# 06-BatteryManagement.net
KiCad netlist of a schematic drawn in Altium Designer
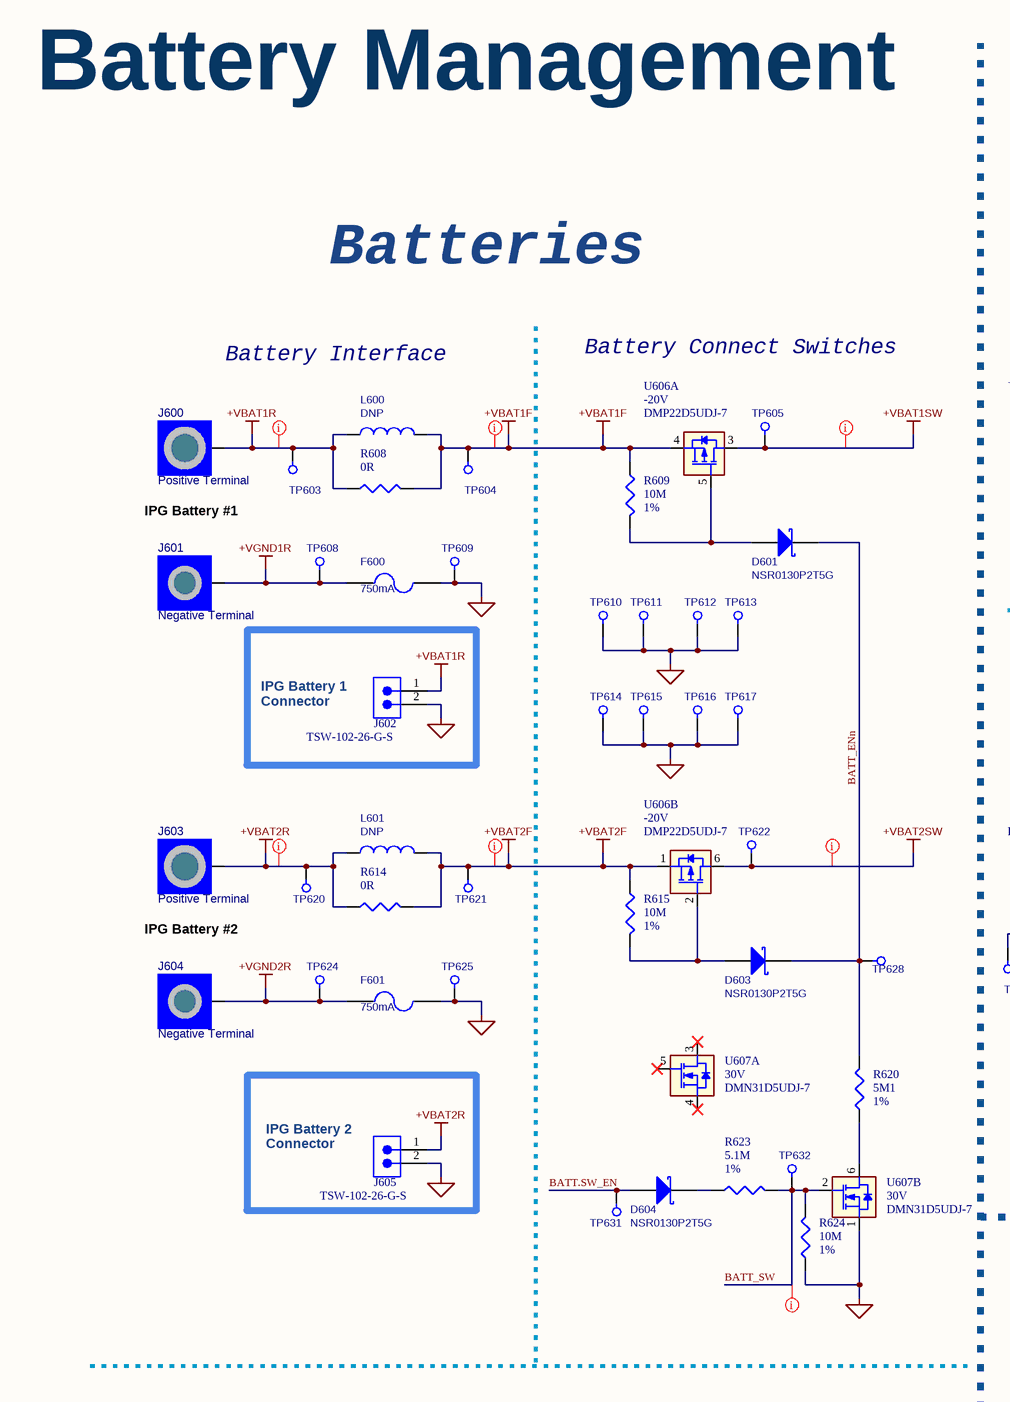
[diagram p0: 06-BatteryManagement.SchDoc, left]
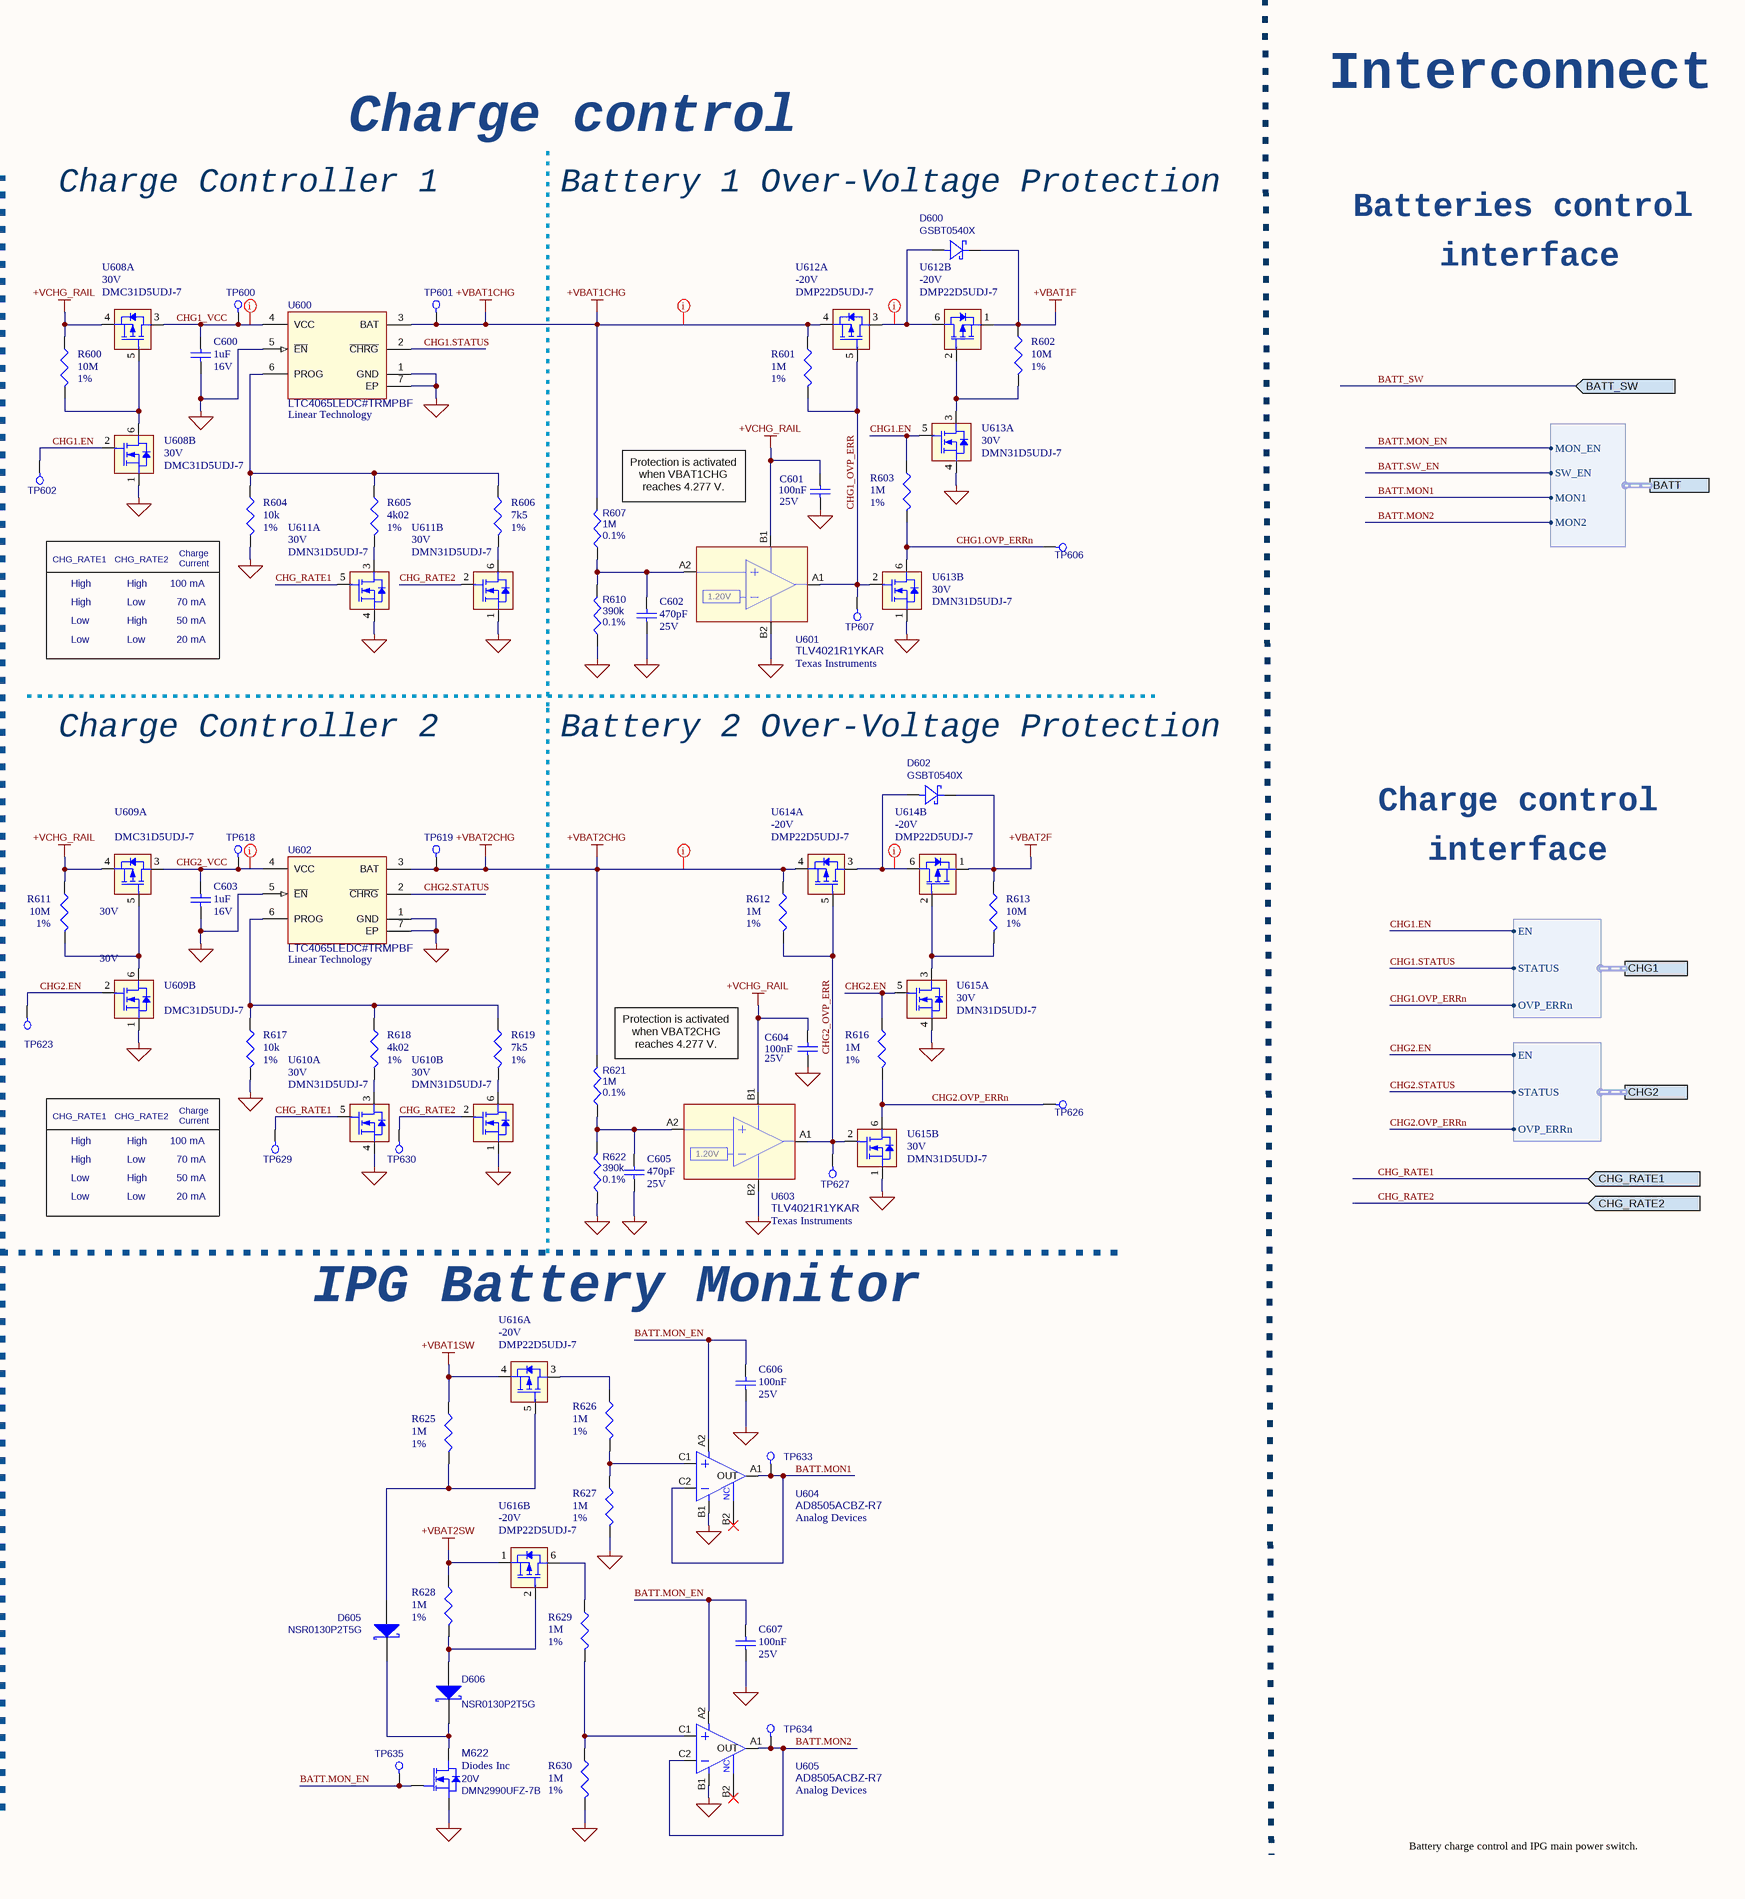
[diagram p1: 06-BatteryManagement.SchDoc, right]

(export (version "E")
  (design (tool "Eeschema 10.0.6"))
  (components
    (comp (ref "C600")
      (value "1uF")
      (footprint "C0201_C")
      (fields
        (field (name "MANUFACTURER") "Murata")
        (field (name "MANUFACTURER PART NUMBER") "GRM033R61C105ME15D")
        (field (name "RATED DC VOLTAGE (URDC)") "16V")
      )
      (libsource (lib "MP-LIBRARY") (part "GRM033R61C105ME15D"))
    )
    (comp (ref "C601")
      (value "100nF")
      (footprint "C0201_C")
      (fields
        (field (name "MANUFACTURER") "Murata")
        (field (name "MANUFACTURER PART NUMBER") "GRM033R61E104KE14J")
        (field (name "RATED DC VOLTAGE (URDC)") "25V")
      )
      (libsource (lib "MP-LIBRARY") (part "GRM033R61E104KE14J"))
    )
    (comp (ref "C602")
      (value "470pF")
      (footprint "C0201_C")
      (fields
        (field (name "MANUFACTURER") "Murata")
        (field (name "MANUFACTURER PART NUMBER") "GCM033R71E471KA03D")
        (field (name "RATED DC VOLTAGE (URDC)") "25V")
      )
      (libsource (lib "MP-LIBRARY") (part "GCM033R71E471KA03D"))
    )
    (comp (ref "C603")
      (value "1uF")
      (footprint "C0201_C")
      (fields
        (field (name "MANUFACTURER") "Murata")
        (field (name "MANUFACTURER PART NUMBER") "GRM033R61C105ME15D")
        (field (name "RATED DC VOLTAGE (URDC)") "16V")
      )
      (libsource (lib "MP-LIBRARY") (part "GRM033R61C105ME15D"))
    )
    (comp (ref "C604")
      (value "100nF")
      (footprint "C0201_C")
      (fields
        (field (name "MANUFACTURER") "Murata")
        (field (name "MANUFACTURER PART NUMBER") "GRM033R61E104KE14J")
        (field (name "RATED DC VOLTAGE (URDC)") "25V")
      )
      (libsource (lib "MP-LIBRARY") (part "GRM033R61E104KE14J"))
    )
    (comp (ref "C605")
      (value "470pF")
      (footprint "C0201_C")
      (fields
        (field (name "MANUFACTURER") "Murata")
        (field (name "MANUFACTURER PART NUMBER") "GCM033R71E471KA03D")
        (field (name "RATED DC VOLTAGE (URDC)") "25V")
      )
      (libsource (lib "MP-LIBRARY") (part "GCM033R71E471KA03D"))
    )
    (comp (ref "C606")
      (value "100nF")
      (footprint "C0201_C")
      (fields
        (field (name "MANUFACTURER") "Murata")
        (field (name "MANUFACTURER PART NUMBER") "GRM033R61E104KE14J")
        (field (name "RATED DC VOLTAGE (URDC)") "25V")
      )
      (libsource (lib "MP-LIBRARY") (part "GRM033R61E104KE14J"))
    )
    (comp (ref "C607")
      (value "100nF")
      (footprint "C0201_C")
      (fields
        (field (name "MANUFACTURER") "Murata")
        (field (name "MANUFACTURER PART NUMBER") "GRM033R61E104KE14J")
        (field (name "RATED DC VOLTAGE (URDC)") "25V")
      )
      (libsource (lib "MP-LIBRARY") (part "GRM033R61E104KE14J"))
    )
    (comp (ref "D600")
      (value "GSBT0540X")
      (footprint "STM_SOD-523_R")
      (description "DIODE SCHOTTKY 40V 500MA SOD523")
      (fields (field (name "MANUFACTURER") "Good-Ark Semiconductor"))
      (libsource (lib "MP-LIBRARY") (part "GSBT0540X"))
    )
    (comp (ref "D601")
      (value "NSR0130P2T5G")
      (footprint "ONSC_SOD-923_CASE514AB")
      (description "Schottky, 30V, 100mA, 385mV, 200mW, SOD-923")
      (fields (field (name "MANUFACTURER") "ON Semiconductor"))
      (libsource (lib "MP-LIBRARY") (part "NSR0130P2T5G"))
    )
    (comp (ref "D602")
      (value "GSBT0540X")
      (footprint "STM_SOD-523_R")
      (description "DIODE SCHOTTKY 40V 500MA SOD523")
      (fields (field (name "MANUFACTURER") "Good-Ark Semiconductor"))
      (libsource (lib "MP-LIBRARY") (part "GSBT0540X"))
    )
    (comp (ref "D603")
      (value "NSR0130P2T5G")
      (footprint "ONSC_SOD-923_CASE514AB")
      (description "Schottky, 30V, 100mA, 385mV, 200mW, SOD-923")
      (fields (field (name "MANUFACTURER") "ON Semiconductor"))
      (libsource (lib "MP-LIBRARY") (part "NSR0130P2T5G"))
    )
    (comp (ref "D604")
      (value "NSR0130P2T5G")
      (footprint "ONSC_SOD-923_CASE514AB")
      (description "Schottky, 30V, 100mA, 385mV, 200mW, SOD-923")
      (fields (field (name "MANUFACTURER") "ON Semiconductor"))
      (libsource (lib "MP-LIBRARY") (part "NSR0130P2T5G"))
    )
    (comp (ref "D605")
      (value "NSR0130P2T5G")
      (footprint "ONSC_SOD-923_CASE514AB")
      (description "Schottky, 30V, 100mA, 385mV, 200mW, SOD-923")
      (fields (field (name "MANUFACTURER") "ON Semiconductor"))
      (libsource (lib "MP-LIBRARY") (part "NSR0130P2T5G"))
    )
    (comp (ref "D606")
      (value "NSR0130P2T5G")
      (footprint "ONSC_SOD-923_CASE514AB")
      (description "Schottky, 30V, 100mA, 385mV, 200mW, SOD-923")
      (fields (field (name "MANUFACTURER") "ON Semiconductor"))
      (libsource (lib "MP-LIBRARY") (part "NSR0130P2T5G"))
    )
    (comp (ref "F600")
      (value "750mA")
      (footprint "LITTELFUSE_440series_1206_REDUCED")
      (description "Fuse, 750mA, 63V, 1206")
      (fields
        (field (name "MANUFACTURER") "Littelfuse")
        (field (name "MANUFACTURER PART NUMBER") "0440.750WR")
      )
      (libsource (lib "MP-LIBRARY") (part "0440.750WR"))
    )
    (comp (ref "F601")
      (value "750mA")
      (footprint "LITTELFUSE_440series_1206_REDUCED")
      (description "Fuse, 750mA, 63V, 1206")
      (fields
        (field (name "MANUFACTURER") "Littelfuse")
        (field (name "MANUFACTURER PART NUMBER") "0440.750WR")
      )
      (libsource (lib "MP-LIBRARY") (part "0440.750WR"))
    )
    (comp (ref "J600")
      (value "Positive Terminal")
      (footprint "Positive_Battery_PTH")
      (description "Positive terminal battery PTH connector for the QL0200I-A battery")
      (fields (field (name "MANUFACTURER") "Quallion") (field (name "MANUFACTURER PART NUMBER") "QL0200I-A"))
      (libsource (lib "MP-LIBRARY") (part "Positive_Battery_PTH"))
    )
    (comp (ref "J601")
      (value "Negative Terminal")
      (footprint "Negative_Battery_PTH")
      (description "Negative terminal battery PTH connector for the QL0200I-A battery")
      (fields (field (name "MANUFACTURER") "Quallion") (field (name "MANUFACTURER PART NUMBER") "QL0200I-A"))
      (libsource (lib "MP-LIBRARY") (part "Negative_Battery_PTH"))
    )
    (comp (ref "J602")
      (value "TSW-102-26-G-S")
      (footprint "SMTC-TSW-102-26-XX-S")
      (description "Conn Unshrouded Header HDR 2 POS 2.54mm Solder ST Thru-Hole")
      (fields (field (name "MANUFACTURER") "Samtec"))
      (libsource (lib "MP-LIBRARY") (part "TSW-102-26-G-S"))
    )
    (comp (ref "J603")
      (value "Positive Terminal")
      (footprint "Positive_Battery_PTH")
      (description "Positive terminal battery PTH connector for the QL0200I-A battery")
      (fields (field (name "MANUFACTURER") "Quallion") (field (name "MANUFACTURER PART NUMBER") "QL0200I-A"))
      (libsource (lib "MP-LIBRARY") (part "Positive_Battery_PTH"))
    )
    (comp (ref "J604")
      (value "Negative Terminal")
      (footprint "Negative_Battery_PTH")
      (description "Negative terminal battery PTH connector for the QL0200I-A battery")
      (fields (field (name "MANUFACTURER") "Quallion") (field (name "MANUFACTURER PART NUMBER") "QL0200I-A"))
      (libsource (lib "MP-LIBRARY") (part "Negative_Battery_PTH"))
    )
    (comp (ref "J605")
      (value "TSW-102-26-G-S")
      (footprint "SMTC-TSW-102-26-XX-S")
      (description "Conn Unshrouded Header HDR 2 POS 2.54mm Solder ST Thru-Hole")
      (fields (field (name "MANUFACTURER") "Samtec"))
      (libsource (lib "MP-LIBRARY") (part "TSW-102-26-G-S"))
    )
    (comp (ref "L600")
      (value "DNP")
      (footprint "L0402_C")
      (description "DNP: Inductor, DNP, 0402")
      (libsource (lib "MP-LIBRARY") (part "IND_DNP_0402"))
    )
    (comp (ref "L601")
      (value "DNP")
      (footprint "L0402_C")
      (description "DNP: Inductor, DNP, 0402")
      (libsource (lib "MP-LIBRARY") (part "IND_DNP_0402"))
    )
    (comp (ref "M622")
      (value "DMN2990UFZ-7B")
      (footprint "DIODESINC_X2-DFN0606-3")
      (description "MOSFET, N-Chan, 20V, 170mA, DFN0606")
      (fields (field (name "MANUFACTURER") "Diodes Inc") (field (name "RATING") "20V"))
      (libsource (lib "MP-LIBRARY") (part "DMN2990UFZ-7B"))
    )
    (comp (ref "R600")
      (value "10M")
      (footprint "R0201_C")
      (fields
        (field (name "MANUFACTURER") "Vishay Draloric")
        (field (name "MANUFACTURER PART NUMBER") "CRCW020110M0FNED")
        (field (name "TOLERANCE") "1%")
        (field (name "POWER") "50mW")
      )
      (libsource (lib "MP-LIBRARY") (part "CRCW020110M0FNED"))
    )
    (comp (ref "R601")
      (value "1M")
      (footprint "R0201_C")
      (fields
        (field (name "MANUFACTURER") "Vishay")
        (field (name "MANUFACTURER PART NUMBER") "CRCW02011M00FNED")
        (field (name "TOLERANCE") "1%")
        (field (name "POWER") "50mW")
      )
      (libsource (lib "MP-LIBRARY") (part "CRCW02011M00FNED"))
    )
    (comp (ref "R602")
      (value "10M")
      (footprint "R0201_C")
      (fields
        (field (name "MANUFACTURER") "Vishay Draloric")
        (field (name "MANUFACTURER PART NUMBER") "CRCW020110M0FNED")
        (field (name "TOLERANCE") "1%")
        (field (name "POWER") "50mW")
      )
      (libsource (lib "MP-LIBRARY") (part "CRCW020110M0FNED"))
    )
    (comp (ref "R603")
      (value "1M")
      (footprint "R0201_C")
      (fields
        (field (name "MANUFACTURER") "Vishay")
        (field (name "MANUFACTURER PART NUMBER") "CRCW02011M00FNED")
        (field (name "TOLERANCE") "1%")
        (field (name "POWER") "50mW")
      )
      (libsource (lib "MP-LIBRARY") (part "CRCW02011M00FNED"))
    )
    (comp (ref "R604")
      (value "10k")
      (footprint "R0201_C")
      (fields
        (field (name "MANUFACTURER") "Vishay")
        (field (name "MANUFACTURER PART NUMBER") "CRCW020110K0FNED")
        (field (name "TOLERANCE") "1%")
        (field (name "POWER") "50mW")
      )
      (libsource (lib "MP-LIBRARY") (part "CRCW020110K0FNED"))
    )
    (comp (ref "R605")
      (value "4k02")
      (footprint "R0201_C")
      (fields
        (field (name "MANUFACTURER") "Vishay")
        (field (name "MANUFACTURER PART NUMBER") "CRCW02014K02FNED")
        (field (name "TOLERANCE") "1%")
        (field (name "POWER") "50mW")
      )
      (libsource (lib "MP-LIBRARY") (part "CRCW02014K02FNED"))
    )
    (comp (ref "R606")
      (value "7k5")
      (footprint "R0201_C")
      (fields
        (field (name "MANUFACTURER") "Vishay")
        (field (name "MANUFACTURER PART NUMBER") "CRCW02017K50FNED")
        (field (name "TOLERANCE") "1%")
        (field (name "POWER") "50mW")
      )
      (libsource (lib "MP-LIBRARY") (part "CRCW02017K50FNED"))
    )
    (comp (ref "R607")
      (value "1M")
      (footprint "R0201_C")
      (description "Resistor, 1M, 0.1%, 0201")
      (fields
        (field (name "MANUFACTURER") "Yageo")
        (field (name "MANUFACTURER PART NUMBER") "RE0201BRE071ML")
        (field (name "PRECISION") "0.1%")
      )
      (libsource (lib "MP-LIBRARY") (part "RE0201BRE071ML"))
    )
    (comp (ref "R608")
      (value "0R")
      (footprint "R0201_C")
      (description "Fixed Resistor, Metal Glaze/thick Film, 0.05W, 0ohm, Surface Mount, 0201")
      (fields
        (field (name "MANUFACTURER") "Vishay")
        (field (name "MANUFACTURER PART NUMBER") "CRCW02010000Z0ED")
      )
      (libsource (lib "MP-LIBRARY") (part "CRCW02010000Z0ED"))
    )
    (comp (ref "R609")
      (value "10M")
      (footprint "R0201_C")
      (fields
        (field (name "MANUFACTURER") "Vishay Draloric")
        (field (name "MANUFACTURER PART NUMBER") "CRCW020110M0FNED")
        (field (name "TOLERANCE") "1%")
        (field (name "POWER") "50mW")
      )
      (libsource (lib "MP-LIBRARY") (part "CRCW020110M0FNED"))
    )
    (comp (ref "R610")
      (value "390k")
      (footprint "R0201_C")
      (description "Resistor, 390k, 0.1%, 0201")
      (fields
        (field (name "MANUFACTURER") "Kamaya")
        (field (name "MANUFACTURER PART NUMBER") "RGC1/20C3903BPA")
        (field (name "PRECISION") "0.1%")
      )
      (libsource (lib "MP-LIBRARY") (part "RGC1/20C3903BPA"))
    )
    (comp (ref "R611")
      (value "10M")
      (footprint "R0201_C")
      (fields
        (field (name "MANUFACTURER") "Vishay Draloric")
        (field (name "MANUFACTURER PART NUMBER") "CRCW020110M0FNED")
        (field (name "TOLERANCE") "1%")
        (field (name "POWER") "50mW")
      )
      (libsource (lib "MP-LIBRARY") (part "CRCW020110M0FNED"))
    )
    (comp (ref "R612")
      (value "1M")
      (footprint "R0201_C")
      (fields
        (field (name "MANUFACTURER") "Vishay")
        (field (name "MANUFACTURER PART NUMBER") "CRCW02011M00FNED")
        (field (name "TOLERANCE") "1%")
        (field (name "POWER") "50mW")
      )
      (libsource (lib "MP-LIBRARY") (part "CRCW02011M00FNED"))
    )
    (comp (ref "R613")
      (value "10M")
      (footprint "R0201_C")
      (fields
        (field (name "MANUFACTURER") "Vishay Draloric")
        (field (name "MANUFACTURER PART NUMBER") "CRCW020110M0FNED")
        (field (name "TOLERANCE") "1%")
        (field (name "POWER") "50mW")
      )
      (libsource (lib "MP-LIBRARY") (part "CRCW020110M0FNED"))
    )
    (comp (ref "R614")
      (value "0R")
      (footprint "R0201_C")
      (description "Fixed Resistor, Metal Glaze/thick Film, 0.05W, 0ohm, Surface Mount, 0201")
      (fields
        (field (name "MANUFACTURER") "Vishay")
        (field (name "MANUFACTURER PART NUMBER") "CRCW02010000Z0ED")
      )
      (libsource (lib "MP-LIBRARY") (part "CRCW02010000Z0ED"))
    )
    (comp (ref "R615")
      (value "10M")
      (footprint "R0201_C")
      (fields
        (field (name "MANUFACTURER") "Vishay Draloric")
        (field (name "MANUFACTURER PART NUMBER") "CRCW020110M0FNED")
        (field (name "TOLERANCE") "1%")
        (field (name "POWER") "50mW")
      )
      (libsource (lib "MP-LIBRARY") (part "CRCW020110M0FNED"))
    )
    (comp (ref "R616")
      (value "1M")
      (footprint "R0201_C")
      (fields
        (field (name "MANUFACTURER") "Vishay")
        (field (name "MANUFACTURER PART NUMBER") "CRCW02011M00FNED")
        (field (name "TOLERANCE") "1%")
        (field (name "POWER") "50mW")
      )
      (libsource (lib "MP-LIBRARY") (part "CRCW02011M00FNED"))
    )
    (comp (ref "R617")
      (value "10k")
      (footprint "R0201_C")
      (fields
        (field (name "MANUFACTURER") "Vishay")
        (field (name "MANUFACTURER PART NUMBER") "CRCW020110K0FNED")
        (field (name "TOLERANCE") "1%")
        (field (name "POWER") "50mW")
      )
      (libsource (lib "MP-LIBRARY") (part "CRCW020110K0FNED"))
    )
    (comp (ref "R618")
      (value "4k02")
      (footprint "R0201_C")
      (fields
        (field (name "MANUFACTURER") "Vishay")
        (field (name "MANUFACTURER PART NUMBER") "CRCW02014K02FNED")
        (field (name "TOLERANCE") "1%")
        (field (name "POWER") "50mW")
      )
      (libsource (lib "MP-LIBRARY") (part "CRCW02014K02FNED"))
    )
    (comp (ref "R619")
      (value "7k5")
      (footprint "R0201_C")
      (fields
        (field (name "MANUFACTURER") "Vishay")
        (field (name "MANUFACTURER PART NUMBER") "CRCW02017K50FNED")
        (field (name "TOLERANCE") "1%")
        (field (name "POWER") "50mW")
      )
      (libsource (lib "MP-LIBRARY") (part "CRCW02017K50FNED"))
    )
    (comp (ref "R620")
      (value "5M1")
      (footprint "R0201_C")
      (fields
        (field (name "MANUFACTURER") "Vishay Draloric")
        (field (name "MANUFACTURER PART NUMBER") "CRCW02015M10FNED")
        (field (name "TOLERANCE") "1%")
        (field (name "POWER") "50mW")
      )
      (libsource (lib "MP-LIBRARY") (part "CRCW02015M10FNED"))
    )
    (comp (ref "R621")
      (value "1M")
      (footprint "R0201_C")
      (description "Resistor, 1M, 0.1%, 0201")
      (fields
        (field (name "MANUFACTURER") "Yageo")
        (field (name "MANUFACTURER PART NUMBER") "RE0201BRE071ML")
        (field (name "PRECISION") "0.1%")
      )
      (libsource (lib "MP-LIBRARY") (part "RE0201BRE071ML"))
    )
    (comp (ref "R622")
      (value "390k")
      (footprint "R0201_C")
      (description "Resistor, 390k, 0.1%, 0201")
      (fields
        (field (name "MANUFACTURER") "Kamaya")
        (field (name "MANUFACTURER PART NUMBER") "RGC1/20C3903BPA")
        (field (name "PRECISION") "0.1%")
      )
      (libsource (lib "MP-LIBRARY") (part "RGC1/20C3903BPA"))
    )
    (comp (ref "R623")
      (value "5.1M")
      (footprint "R0201_C")
      (fields
        (field (name "MANUFACTURER") "Vishay Draloric")
        (field (name "MANUFACTURER PART NUMBER") "CRCW02015M10FNED")
        (field (name "TOLERANCE") "1%")
        (field (name "POWER") "50mW")
      )
      (libsource (lib "MP-LIBRARY") (part "CRCW02015M10FNED"))
    )
    (comp (ref "R624")
      (value "10M")
      (footprint "R0201_C")
      (fields
        (field (name "MANUFACTURER") "Vishay Draloric")
        (field (name "MANUFACTURER PART NUMBER") "CRCW020110M0FNED")
        (field (name "TOLERANCE") "1%")
        (field (name "POWER") "50mW")
      )
      (libsource (lib "MP-LIBRARY") (part "CRCW020110M0FNED"))
    )
    (comp (ref "R625")
      (value "1M")
      (footprint "R0201_C")
      (fields
        (field (name "MANUFACTURER") "Vishay")
        (field (name "MANUFACTURER PART NUMBER") "CRCW02011M00FNED")
        (field (name "TOLERANCE") "1%")
        (field (name "POWER") "50mW")
      )
      (libsource (lib "MP-LIBRARY") (part "CRCW02011M00FNED"))
    )
    (comp (ref "R626")
      (value "1M")
      (footprint "R0201_C")
      (fields
        (field (name "MANUFACTURER") "Vishay")
        (field (name "MANUFACTURER PART NUMBER") "CRCW02011M00FNED")
        (field (name "TOLERANCE") "1%")
        (field (name "POWER") "50mW")
      )
      (libsource (lib "MP-LIBRARY") (part "CRCW02011M00FNED"))
    )
    (comp (ref "R627")
      (value "1M")
      (footprint "R0201_C")
      (fields
        (field (name "MANUFACTURER") "Vishay")
        (field (name "MANUFACTURER PART NUMBER") "CRCW02011M00FNED")
        (field (name "TOLERANCE") "1%")
        (field (name "POWER") "50mW")
      )
      (libsource (lib "MP-LIBRARY") (part "CRCW02011M00FNED"))
    )
    (comp (ref "R628")
      (value "1M")
      (footprint "R0201_C")
      (fields
        (field (name "MANUFACTURER") "Vishay")
        (field (name "MANUFACTURER PART NUMBER") "CRCW02011M00FNED")
        (field (name "TOLERANCE") "1%")
        (field (name "POWER") "50mW")
      )
      (libsource (lib "MP-LIBRARY") (part "CRCW02011M00FNED"))
    )
    (comp (ref "R629")
      (value "1M")
      (footprint "R0201_C")
      (fields
        (field (name "MANUFACTURER") "Vishay")
        (field (name "MANUFACTURER PART NUMBER") "CRCW02011M00FNED")
        (field (name "TOLERANCE") "1%")
        (field (name "POWER") "50mW")
      )
      (libsource (lib "MP-LIBRARY") (part "CRCW02011M00FNED"))
    )
    (comp (ref "R630")
      (value "1M")
      (footprint "R0201_C")
      (fields
        (field (name "MANUFACTURER") "Vishay")
        (field (name "MANUFACTURER PART NUMBER") "CRCW02011M00FNED")
        (field (name "TOLERANCE") "1%")
        (field (name "POWER") "50mW")
      )
      (libsource (lib "MP-LIBRARY") (part "CRCW02011M00FNED"))
    )
    (comp (ref "TP600")
      (value "Test Point")
      (footprint "testpad_0.9mm")
      (description "Test pad, 0.90mm circular pad")
      (libsource (lib "MP-LIBRARY") (part "Test Point"))
    )
    (comp (ref "TP601")
      (value "Test Point")
      (footprint "testpad_0.9mm")
      (description "Test pad, 0.90mm circular pad")
      (libsource (lib "MP-LIBRARY") (part "Test Point"))
    )
    (comp (ref "TP602")
      (value "Test Point")
      (footprint "testpad_0.9mm")
      (description "Test pad, 0.90mm circular pad")
      (libsource (lib "MP-LIBRARY") (part "Test Point"))
    )
    (comp (ref "TP603")
      (value "Test Point")
      (footprint "testpad_0.9mm")
      (description "Test pad, 0.90mm circular pad")
      (libsource (lib "MP-LIBRARY") (part "Test Point"))
    )
    (comp (ref "TP604")
      (value "Test Point")
      (footprint "testpad_0.9mm")
      (description "Test pad, 0.90mm circular pad")
      (libsource (lib "MP-LIBRARY") (part "Test Point"))
    )
    (comp (ref "TP605")
      (value "Test Point")
      (footprint "testpad_0.9mm")
      (description "Test pad, 0.90mm circular pad")
      (libsource (lib "MP-LIBRARY") (part "Test Point"))
    )
    (comp (ref "TP606")
      (value "Test Point")
      (footprint "testpad_0.9mm")
      (description "Test pad, 0.90mm circular pad")
      (libsource (lib "MP-LIBRARY") (part "Test Point"))
    )
    (comp (ref "TP607")
      (value "Test Point")
      (footprint "testpad_0.9mm")
      (description "Test pad, 0.90mm circular pad")
      (libsource (lib "MP-LIBRARY") (part "Test Point"))
    )
    (comp (ref "TP608")
      (value "Test Point")
      (footprint "testpad_0.9mm")
      (description "Test pad, 0.90mm circular pad")
      (libsource (lib "MP-LIBRARY") (part "Test Point"))
    )
    (comp (ref "TP609")
      (value "Test Point")
      (footprint "testpad_0.9mm")
      (description "Test pad, 0.90mm circular pad")
      (libsource (lib "MP-LIBRARY") (part "Test Point"))
    )
    (comp (ref "TP610")
      (value "Test Point")
      (footprint "testpad_0.9mm")
      (description "Test pad, 0.90mm circular pad")
      (libsource (lib "MP-LIBRARY") (part "Test Point"))
    )
    (comp (ref "TP611")
      (value "Test Point")
      (footprint "testpad_0.9mm")
      (description "Test pad, 0.90mm circular pad")
      (libsource (lib "MP-LIBRARY") (part "Test Point"))
    )
    (comp (ref "TP612")
      (value "Test Point")
      (footprint "testpad_0.9mm")
      (description "Test pad, 0.90mm circular pad")
      (libsource (lib "MP-LIBRARY") (part "Test Point"))
    )
    (comp (ref "TP613")
      (value "Test Point")
      (footprint "testpad_0.9mm")
      (description "Test pad, 0.90mm circular pad")
      (libsource (lib "MP-LIBRARY") (part "Test Point"))
    )
    (comp (ref "TP614")
      (value "Test Point")
      (footprint "testpad_0.9mm")
      (description "Test pad, 0.90mm circular pad")
      (libsource (lib "MP-LIBRARY") (part "Test Point"))
    )
    (comp (ref "TP615")
      (value "Test Point")
      (footprint "testpad_0.9mm")
      (description "Test pad, 0.90mm circular pad")
      (libsource (lib "MP-LIBRARY") (part "Test Point"))
    )
    (comp (ref "TP616")
      (value "Test Point")
      (footprint "testpad_0.9mm")
      (description "Test pad, 0.90mm circular pad")
      (libsource (lib "MP-LIBRARY") (part "Test Point"))
    )
    (comp (ref "TP617")
      (value "Test Point")
      (footprint "testpad_0.9mm")
      (description "Test pad, 0.90mm circular pad")
      (libsource (lib "MP-LIBRARY") (part "Test Point"))
    )
    (comp (ref "TP618")
      (value "Test Point")
      (footprint "testpad_0.9mm")
      (description "Test pad, 0.90mm circular pad")
      (libsource (lib "MP-LIBRARY") (part "Test Point"))
    )
    (comp (ref "TP619")
      (value "Test Point")
      (footprint "testpad_0.9mm")
      (description "Test pad, 0.90mm circular pad")
      (libsource (lib "MP-LIBRARY") (part "Test Point"))
    )
    (comp (ref "TP620")
      (value "Test Point")
      (footprint "testpad_0.9mm")
      (description "Test pad, 0.90mm circular pad")
      (libsource (lib "MP-LIBRARY") (part "Test Point"))
    )
    (comp (ref "TP621")
      (value "Test Point")
      (footprint "testpad_0.9mm")
      (description "Test pad, 0.90mm circular pad")
      (libsource (lib "MP-LIBRARY") (part "Test Point"))
    )
    (comp (ref "TP622")
      (value "Test Point")
      (footprint "testpad_0.9mm")
      (description "Test pad, 0.90mm circular pad")
      (libsource (lib "MP-LIBRARY") (part "Test Point"))
    )
    (comp (ref "TP623")
      (value "Test Point")
      (footprint "testpad_0.9mm")
      (description "Test pad, 0.90mm circular pad")
      (libsource (lib "MP-LIBRARY") (part "Test Point"))
    )
    (comp (ref "TP624")
      (value "Test Point")
      (footprint "testpad_0.9mm")
      (description "Test pad, 0.90mm circular pad")
      (libsource (lib "MP-LIBRARY") (part "Test Point"))
    )
    (comp (ref "TP625")
      (value "Test Point")
      (footprint "testpad_0.9mm")
      (description "Test pad, 0.90mm circular pad")
      (libsource (lib "MP-LIBRARY") (part "Test Point"))
    )
    (comp (ref "TP626")
      (value "Test Point")
      (footprint "testpad_0.9mm")
      (description "Test pad, 0.90mm circular pad")
      (libsource (lib "MP-LIBRARY") (part "Test Point"))
    )
    (comp (ref "TP627")
      (value "Test Point")
      (footprint "testpad_0.9mm")
      (description "Test pad, 0.90mm circular pad")
      (libsource (lib "MP-LIBRARY") (part "Test Point"))
    )
    (comp (ref "TP628")
      (value "Test Point")
      (footprint "testpad_0.9mm")
      (description "Test pad, 0.90mm circular pad")
      (libsource (lib "MP-LIBRARY") (part "Test Point"))
    )
    (comp (ref "TP629")
      (value "Test Point")
      (footprint "testpad_0.9mm")
      (description "Test pad, 0.90mm circular pad")
      (libsource (lib "MP-LIBRARY") (part "Test Point"))
    )
    (comp (ref "TP630")
      (value "Test Point")
      (footprint "testpad_0.9mm")
      (description "Test pad, 0.90mm circular pad")
      (libsource (lib "MP-LIBRARY") (part "Test Point"))
    )
    (comp (ref "TP631")
      (value "Test Point")
      (footprint "testpad_0.9mm")
      (description "Test pad, 0.90mm circular pad")
      (libsource (lib "MP-LIBRARY") (part "Test Point"))
    )
    (comp (ref "TP632")
      (value "Test Point")
      (footprint "testpad_0.9mm")
      (description "Test pad, 0.90mm circular pad")
      (libsource (lib "MP-LIBRARY") (part "Test Point"))
    )
    (comp (ref "TP633")
      (value "Test Point")
      (footprint "testpad_0.9mm")
      (description "Test pad, 0.90mm circular pad")
      (libsource (lib "MP-LIBRARY") (part "Test Point"))
    )
    (comp (ref "TP634")
      (value "Test Point")
      (footprint "testpad_0.9mm")
      (description "Test pad, 0.90mm circular pad")
      (libsource (lib "MP-LIBRARY") (part "Test Point"))
    )
    (comp (ref "TP635")
      (value "Test Point")
      (footprint "testpad_0.9mm")
      (description "Test pad, 0.90mm circular pad")
      (libsource (lib "MP-LIBRARY") (part "Test Point"))
    )
    (comp (ref "U600")
      (value "LTC4065LEDC#TRMPBF")
      (footprint "LT_DC6")
      (description "Charge Controller, 4.2V, 250mA, DFN-6")
      (fields
        (field (name "MANUFACTURER") "Linear Technology")
        (field (name "MANUFACTURER PART NUMBER") "LTC4065LEDC#TRPBF")
      )
      (libsource (lib "MP-LIBRARY") (part "LTC4065LEDC#TRPBF"))
    )
    (comp (ref "U601")
      (value "TLV4021R1YKAR")
      (footprint "TI_YKA0004")
      (description "Comparator, 1.2V Reference, Open-drain, BGA-4")
      (fields (field (name "MANUFACTURER") "Texas Instruments"))
      (libsource (lib "MP-LIBRARY") (part "TLV4021R1YKAR"))
    )
    (comp (ref "U602")
      (value "LTC4065LEDC#TRMPBF")
      (footprint "LT_DC6")
      (description "Charge Controller, 4.2V, 250mA, DFN-6")
      (fields
        (field (name "MANUFACTURER") "Linear Technology")
        (field (name "MANUFACTURER PART NUMBER") "LTC4065LEDC#TRPBF")
      )
      (libsource (lib "MP-LIBRARY") (part "LTC4065LEDC#TRPBF"))
    )
    (comp (ref "U603")
      (value "TLV4021R1YKAR")
      (footprint "TI_YKA0004")
      (description "Comparator, 1.2V Reference, Open-drain, BGA-4")
      (fields (field (name "MANUFACTURER") "Texas Instruments"))
      (libsource (lib "MP-LIBRARY") (part "TLV4021R1YKAR"))
    )
    (comp (ref "U604")
      (value "AD8505ACBZ-R7")
      (footprint "AD8505ACBZ-R7")
      (description "Op Amp, Rail-to-Rail, 95kHz, WLCSP-6")
      (fields (field (name "MANUFACTURER") "Analog Devices"))
      (libsource (lib "MP-LIBRARY") (part "AD8505ACBZ-R7"))
    )
    (comp (ref "U605")
      (value "AD8505ACBZ-R7")
      (footprint "AD8505ACBZ-R7")
      (description "Op Amp, Rail-to-Rail, 95kHz, WLCSP-6")
      (fields (field (name "MANUFACTURER") "Analog Devices"))
      (libsource (lib "MP-LIBRARY") (part "AD8505ACBZ-R7"))
    )
    (comp (ref "U606")
      (value "DMP22D5UDJ-7")
      (footprint "DIODESINC_SOT-963-6")
      (description "MOSFET 2P-CH 20V 0.36A SOT963")
      (fields (field (name "MANUFACTURER") "Diodes inc.") (field (name "VDS(MAX)") "-20V"))
      (libsource (lib "") (part "DMP22D5UDJ-7_1"))
    )
    (comp (ref "U607")
      (value "DMN31D5UDJ-7")
      (footprint "DIODESINC_SOT-963-6")
      (description "MOSFET 2N-CH 30V 0.22A SOT963")
      (fields (field (name "MANUFACTURER") "Diodes inc.") (field (name "VDS(MAX)") "30V"))
      (libsource (lib "MP-LIBRARY") (part "DMN31D5UDJ-7"))
    )
    (comp (ref "U608")
      (value "DMC31D5UDJ-7")
      (footprint "DIODESINC_SOT-963-6")
      (description "MOSFET N/P-CH 30V 0.22A SOT963")
      (fields (field (name "MANUFACTURER") "Diodes inc.") (field (name "VDS(MAX)") "30V"))
      (libsource (lib "MP-LIBRARY") (part "DMC31D5UDJ-7"))
    )
    (comp (ref "U609")
      (value "DMC31D5UDJ-7")
      (footprint "DIODESINC_SOT-963-6")
      (description "MOSFET N/P-CH 30V 0.22A SOT963")
      (fields (field (name "MANUFACTURER") "Diodes inc.") (field (name "VDS(MAX)") "30V"))
      (libsource (lib "MP-LIBRARY") (part "DMC31D5UDJ-7"))
    )
    (comp (ref "U610")
      (value "DMN31D5UDJ-7")
      (footprint "DIODESINC_SOT-963-6")
      (description "MOSFET 2N-CH 30V 0.22A SOT963")
      (fields (field (name "MANUFACTURER") "Diodes inc.") (field (name "VDS(MAX)") "30V"))
      (libsource (lib "MP-LIBRARY") (part "DMN31D5UDJ-7"))
    )
    (comp (ref "U611")
      (value "DMN31D5UDJ-7")
      (footprint "DIODESINC_SOT-963-6")
      (description "MOSFET 2N-CH 30V 0.22A SOT963")
      (fields (field (name "MANUFACTURER") "Diodes inc.") (field (name "VDS(MAX)") "30V"))
      (libsource (lib "MP-LIBRARY") (part "DMN31D5UDJ-7"))
    )
    (comp (ref "U612")
      (value "DMP22D5UDJ-7")
      (footprint "DIODESINC_SOT-963-6")
      (description "MOSFET 2P-CH 20V 0.36A SOT963")
      (fields (field (name "MANUFACTURER") "Diodes inc.") (field (name "VDS(MAX)") "-20V"))
      (libsource (lib "") (part "DMP22D5UDJ-7_1"))
    )
    (comp (ref "U613")
      (value "DMN31D5UDJ-7")
      (footprint "DIODESINC_SOT-963-6")
      (description "MOSFET 2N-CH 30V 0.22A SOT963")
      (fields (field (name "MANUFACTURER") "Diodes inc.") (field (name "VDS(MAX)") "30V"))
      (libsource (lib "MP-LIBRARY") (part "DMN31D5UDJ-7"))
    )
    (comp (ref "U614")
      (value "DMP22D5UDJ-7")
      (footprint "DIODESINC_SOT-963-6")
      (description "MOSFET 2P-CH 20V 0.36A SOT963")
      (fields (field (name "MANUFACTURER") "Diodes inc.") (field (name "VDS(MAX)") "-20V"))
      (libsource (lib "MP-LIBRARY") (part "DMP22D5UDJ-7"))
    )
    (comp (ref "U615")
      (value "DMN31D5UDJ-7")
      (footprint "DIODESINC_SOT-963-6")
      (description "MOSFET 2N-CH 30V 0.22A SOT963")
      (fields (field (name "MANUFACTURER") "Diodes inc.") (field (name "VDS(MAX)") "30V"))
      (libsource (lib "MP-LIBRARY") (part "DMN31D5UDJ-7"))
    )
    (comp (ref "U616")
      (value "DMP22D5UDJ-7")
      (footprint "DIODESINC_SOT-963-6")
      (description "MOSFET 2P-CH 20V 0.36A SOT963")
      (fields (field (name "MANUFACTURER") "Diodes inc.") (field (name "VDS(MAX)") "-20V"))
      (libsource (lib "") (part "DMP22D5UDJ-7_1"))
    )
  )
  (nets
    (net (code "3") (name "+VBAT1CHG") (class "Default")
      (node (ref "R601") (pin "1") (pinfunction "1_1") (pintype "passive"))
      (node (ref "R607") (pin "2") (pinfunction "2_2") (pintype "passive"))
      (node (ref "TP601") (pin "1") (pinfunction "1_1") (pintype "passive"))
      (node (ref "U600") (pin "3") (pinfunction "BAT_3") (pintype "power_in"))
      (node (ref "U612") (pin "4") (pinfunction "4_4") (pintype "passive"))
    )
    (net (code "4") (name "+VBAT1F") (class "Default")
      (node (ref "D600") (pin "1") (pinfunction "1_1") (pintype "passive"))
      (node (ref "L600") (pin "2") (pinfunction "2_2") (pintype "passive"))
      (node (ref "R602") (pin "1") (pinfunction "1_1") (pintype "passive"))
      (node (ref "R608") (pin "2") (pinfunction "2_2") (pintype "passive"))
      (node (ref "R609") (pin "1") (pinfunction "1_1") (pintype "passive"))
      (node (ref "TP604") (pin "1") (pinfunction "1_1") (pintype "passive"))
      (node (ref "U606") (pin "4") (pinfunction "4_4") (pintype "passive"))
      (node (ref "U612") (pin "1") (pinfunction "1_1") (pintype "passive"))
    )
    (net (code "5") (name "+VBAT1R") (class "Default")
      (node (ref "J600") (pin "1") (pinfunction "1_1") (pintype "passive"))
      (node (ref "J602") (pin "1") (pinfunction "1_1") (pintype "passive"))
      (node (ref "L600") (pin "1") (pinfunction "1_1") (pintype "passive"))
      (node (ref "R608") (pin "1") (pinfunction "1_1") (pintype "passive"))
      (node (ref "TP603") (pin "1") (pinfunction "1_1") (pintype "passive"))
    )
    (net (code "6") (name "+VBAT1SW") (class "Default")
      (node (ref "R625") (pin "1") (pinfunction "1_1") (pintype "passive"))
      (node (ref "TP605") (pin "1") (pinfunction "1_1") (pintype "passive"))
      (node (ref "U606") (pin "3") (pinfunction "3_3") (pintype "passive"))
      (node (ref "U616") (pin "4") (pinfunction "4_4") (pintype "passive"))
    )
    (net (code "7") (name "+VBAT2CHG") (class "Default")
      (node (ref "R612") (pin "1") (pinfunction "1_1") (pintype "passive"))
      (node (ref "R621") (pin "2") (pinfunction "2_2") (pintype "passive"))
      (node (ref "TP619") (pin "1") (pinfunction "1_1") (pintype "passive"))
      (node (ref "U602") (pin "3") (pinfunction "BAT_3") (pintype "power_in"))
      (node (ref "U614") (pin "4") (pinfunction "4_4") (pintype "passive"))
    )
    (net (code "8") (name "+VBAT2F") (class "Default")
      (node (ref "D602") (pin "1") (pinfunction "1_1") (pintype "passive"))
      (node (ref "L601") (pin "2") (pinfunction "2_2") (pintype "passive"))
      (node (ref "R613") (pin "1") (pinfunction "1_1") (pintype "passive"))
      (node (ref "R614") (pin "2") (pinfunction "2_2") (pintype "passive"))
      (node (ref "R615") (pin "1") (pinfunction "1_1") (pintype "passive"))
      (node (ref "TP621") (pin "1") (pinfunction "1_1") (pintype "passive"))
      (node (ref "U606") (pin "1") (pinfunction "1_1") (pintype "passive"))
      (node (ref "U614") (pin "1") (pinfunction "1_1") (pintype "passive"))
    )
    (net (code "9") (name "+VBAT2R") (class "Default")
      (node (ref "J603") (pin "1") (pinfunction "1_1") (pintype "passive"))
      (node (ref "J605") (pin "1") (pinfunction "1_1") (pintype "passive"))
      (node (ref "L601") (pin "1") (pinfunction "1_1") (pintype "passive"))
      (node (ref "R614") (pin "1") (pinfunction "1_1") (pintype "passive"))
      (node (ref "TP620") (pin "1") (pinfunction "1_1") (pintype "passive"))
    )
    (net (code "10") (name "+VBAT2SW") (class "Default")
      (node (ref "R628") (pin "1") (pinfunction "1_1") (pintype "passive"))
      (node (ref "TP622") (pin "1") (pinfunction "1_1") (pintype "passive"))
      (node (ref "U606") (pin "6") (pinfunction "6_6") (pintype "passive"))
      (node (ref "U616") (pin "1") (pinfunction "1_1") (pintype "passive"))
    )
    (net (code "11") (name "+VCHG_RAIL") (class "Default")
      (node (ref "C601") (pin "2") (pinfunction "2_2") (pintype "passive"))
      (node (ref "C604") (pin "2") (pinfunction "2_2") (pintype "passive"))
      (node (ref "R600") (pin "1") (pinfunction "1_1") (pintype "passive"))
      (node (ref "R611") (pin "1") (pinfunction "1_1") (pintype "passive"))
      (node (ref "U601") (pin "B1") (pinfunction "V+_B1") (pintype "power_in"))
      (node (ref "U603") (pin "B1") (pinfunction "V+_B1") (pintype "power_in"))
      (node (ref "U608") (pin "4") (pinfunction "4_4") (pintype "passive"))
      (node (ref "U609") (pin "4") (pinfunction "4_4") (pintype "passive"))
    )
    (net (code "12") (name "+VGND1R") (class "Default")
      (node (ref "F600") (pin "1") (pinfunction "1_1") (pintype "passive"))
      (node (ref "J601") (pin "1") (pinfunction "1_1") (pintype "passive"))
      (node (ref "TP608") (pin "1") (pinfunction "1_1") (pintype "passive"))
    )
    (net (code "13") (name "+VGND2R") (class "Default")
      (node (ref "F601") (pin "1") (pinfunction "1_1") (pintype "passive"))
      (node (ref "J604") (pin "1") (pinfunction "1_1") (pintype "passive"))
      (node (ref "TP624") (pin "1") (pinfunction "1_1") (pintype "passive"))
    )
    (net (code "14") (name "/BATT.MON1") (class "Default")
      (node (ref "TP633") (pin "1") (pinfunction "1_1") (pintype "passive"))
      (node (ref "U604") (pin "A1") (pinfunction "OUT_A1") (pintype "passive"))
      (node (ref "U604") (pin "C2") (pinfunction "IN-_C2") (pintype "passive"))
    )
    (net (code "15") (name "/BATT.MON2") (class "Default")
      (node (ref "TP634") (pin "1") (pinfunction "1_1") (pintype "passive"))
      (node (ref "U605") (pin "A1") (pinfunction "OUT_A1") (pintype "passive"))
      (node (ref "U605") (pin "C2") (pinfunction "IN-_C2") (pintype "passive"))
    )
    (net (code "16") (name "/BATT.MON_EN") (class "Default")
      (node (ref "C606") (pin "2") (pinfunction "2_2") (pintype "passive"))
      (node (ref "C607") (pin "2") (pinfunction "2_2") (pintype "passive"))
      (node (ref "M622") (pin "1") (pinfunction "G_1") (pintype "passive"))
      (node (ref "TP635") (pin "1") (pinfunction "1_1") (pintype "passive"))
      (node (ref "U604") (pin "A2") (pinfunction "V+_A2") (pintype "power_in"))
      (node (ref "U605") (pin "A2") (pinfunction "V+_A2") (pintype "power_in"))
    )
    (net (code "17") (name "/BATT.SW_EN") (class "Default")
      (node (ref "D604") (pin "2") (pinfunction "A_2") (pintype "passive"))
      (node (ref "TP631") (pin "1") (pinfunction "1_1") (pintype "passive"))
    )
    (net (code "18") (name "/BATT_ENn") (class "Default")
      (node (ref "D601") (pin "1") (pinfunction "K_1") (pintype "passive"))
      (node (ref "D603") (pin "1") (pinfunction "K_1") (pintype "passive"))
      (node (ref "R620") (pin "2") (pinfunction "2_2") (pintype "passive"))
      (node (ref "TP628") (pin "1") (pinfunction "1_1") (pintype "passive"))
    )
    (net (code "19") (name "/BATT_SW") (class "Default")
      (node (ref "R623") (pin "2") (pinfunction "2_2") (pintype "passive"))
      (node (ref "R624") (pin "2") (pinfunction "2_2") (pintype "passive"))
      (node (ref "TP632") (pin "1") (pinfunction "1_1") (pintype "passive"))
      (node (ref "U607") (pin "2") (pinfunction "2_2") (pintype "passive"))
    )
    (net (code "20") (name "/CHG1.EN") (class "Default")
      (node (ref "R603") (pin "1") (pinfunction "1_1") (pintype "passive"))
      (node (ref "TP602") (pin "1") (pinfunction "1_1") (pintype "passive"))
      (node (ref "U608") (pin "2") (pinfunction "2_2") (pintype "passive"))
      (node (ref "U613") (pin "5") (pinfunction "5_5") (pintype "passive"))
    )
    (net (code "21") (name "/CHG1.OVP_ERRn") (class "Default")
      (node (ref "R603") (pin "2") (pinfunction "2_2") (pintype "passive"))
      (node (ref "TP606") (pin "1") (pinfunction "1_1") (pintype "passive"))
      (node (ref "U613") (pin "6") (pinfunction "6_6") (pintype "passive"))
    )
    (net (code "22") (name "/CHG1.STATUS") (class "Default")
      (node (ref "U600") (pin "2") (pinfunction "~{CHRG}_2") (pintype "open_collector"))
    )
    (net (code "23") (name "/CHG1_OVP_ERR") (class "Default")
      (node (ref "R601") (pin "2") (pinfunction "2_2") (pintype "passive"))
      (node (ref "TP607") (pin "1") (pinfunction "1_1") (pintype "passive"))
      (node (ref "U601") (pin "A1") (pinfunction "OUT_A1") (pintype "power_in"))
      (node (ref "U612") (pin "5") (pinfunction "5_5") (pintype "passive"))
      (node (ref "U613") (pin "2") (pinfunction "2_2") (pintype "passive"))
    )
    (net (code "24") (name "/CHG1_VCC") (class "Default")
      (node (ref "C600") (pin "1") (pinfunction "1_1") (pintype "passive"))
      (node (ref "TP600") (pin "1") (pinfunction "1_1") (pintype "passive"))
      (node (ref "U600") (pin "4") (pinfunction "VCC_4") (pintype "power_in"))
      (node (ref "U608") (pin "3") (pinfunction "3_3") (pintype "passive"))
    )
    (net (code "25") (name "/CHG2.EN") (class "Default")
      (node (ref "R616") (pin "1") (pinfunction "1_1") (pintype "passive"))
      (node (ref "TP623") (pin "1") (pinfunction "1_1") (pintype "passive"))
      (node (ref "U609") (pin "2") (pinfunction "2_2") (pintype "passive"))
      (node (ref "U615") (pin "5") (pinfunction "5_5") (pintype "passive"))
    )
    (net (code "26") (name "/CHG2.OVP_ERRn") (class "Default")
      (node (ref "R616") (pin "2") (pinfunction "2_2") (pintype "passive"))
      (node (ref "TP626") (pin "1") (pinfunction "1_1") (pintype "passive"))
      (node (ref "U615") (pin "6") (pinfunction "6_6") (pintype "passive"))
    )
    (net (code "27") (name "/CHG2.STATUS") (class "Default")
      (node (ref "U602") (pin "2") (pinfunction "~{CHRG}_2") (pintype "open_collector"))
    )
    (net (code "28") (name "/CHG2_OVP_ERR") (class "Default")
      (node (ref "R612") (pin "2") (pinfunction "2_2") (pintype "passive"))
      (node (ref "TP627") (pin "1") (pinfunction "1_1") (pintype "passive"))
      (node (ref "U603") (pin "A1") (pinfunction "OUT_A1") (pintype "power_in"))
      (node (ref "U614") (pin "5") (pinfunction "5_5") (pintype "passive"))
      (node (ref "U615") (pin "2") (pinfunction "2_2") (pintype "passive"))
    )
    (net (code "29") (name "/CHG2_VCC") (class "Default")
      (node (ref "C603") (pin "1") (pinfunction "1_1") (pintype "passive"))
      (node (ref "TP618") (pin "1") (pinfunction "1_1") (pintype "passive"))
      (node (ref "U602") (pin "4") (pinfunction "VCC_4") (pintype "power_in"))
      (node (ref "U609") (pin "3") (pinfunction "3_3") (pintype "passive"))
    )
    (net (code "30") (name "/CHG_RATE1") (class "Default")
      (node (ref "TP629") (pin "1") (pinfunction "1_1") (pintype "passive"))
      (node (ref "U610") (pin "5") (pinfunction "5_5") (pintype "passive"))
      (node (ref "U611") (pin "5") (pinfunction "5_5") (pintype "passive"))
    )
    (net (code "31") (name "/CHG_RATE2") (class "Default")
      (node (ref "TP630") (pin "1") (pinfunction "1_1") (pintype "passive"))
      (node (ref "U610") (pin "2") (pinfunction "2_2") (pintype "passive"))
      (node (ref "U611") (pin "2") (pinfunction "2_2") (pintype "passive"))
    )
    (net (code "34") (name "GND") (class "Default")
      (node (ref "C600") (pin "2") (pinfunction "2_2") (pintype "passive"))
      (node (ref "C601") (pin "1") (pinfunction "1_1") (pintype "passive"))
      (node (ref "C602") (pin "1") (pinfunction "1_1") (pintype "passive"))
      (node (ref "C603") (pin "2") (pinfunction "2_2") (pintype "passive"))
      (node (ref "C604") (pin "1") (pinfunction "1_1") (pintype "passive"))
      (node (ref "C605") (pin "1") (pinfunction "1_1") (pintype "passive"))
      (node (ref "C606") (pin "1") (pinfunction "1_1") (pintype "passive"))
      (node (ref "C607") (pin "1") (pinfunction "1_1") (pintype "passive"))
      (node (ref "F600") (pin "2") (pinfunction "2_2") (pintype "passive"))
      (node (ref "F601") (pin "2") (pinfunction "2_2") (pintype "passive"))
      (node (ref "J602") (pin "2") (pinfunction "2_2") (pintype "passive"))
      (node (ref "J605") (pin "2") (pinfunction "2_2") (pintype "passive"))
      (node (ref "M622") (pin "2") (pinfunction "S_2") (pintype "passive"))
      (node (ref "R604") (pin "2") (pinfunction "2_2") (pintype "passive"))
      (node (ref "R610") (pin "1") (pinfunction "1_1") (pintype "passive"))
      (node (ref "R617") (pin "2") (pinfunction "2_2") (pintype "passive"))
      (node (ref "R622") (pin "1") (pinfunction "1_1") (pintype "passive"))
      (node (ref "R624") (pin "1") (pinfunction "1_1") (pintype "passive"))
      (node (ref "R627") (pin "2") (pinfunction "2_2") (pintype "passive"))
      (node (ref "R630") (pin "2") (pinfunction "2_2") (pintype "passive"))
      (node (ref "TP609") (pin "1") (pinfunction "1_1") (pintype "passive"))
      (node (ref "TP610") (pin "1") (pinfunction "1_1") (pintype "passive"))
      (node (ref "TP611") (pin "1") (pinfunction "1_1") (pintype "passive"))
      (node (ref "TP612") (pin "1") (pinfunction "1_1") (pintype "passive"))
      (node (ref "TP613") (pin "1") (pinfunction "1_1") (pintype "passive"))
      (node (ref "TP614") (pin "1") (pinfunction "1_1") (pintype "passive"))
      (node (ref "TP615") (pin "1") (pinfunction "1_1") (pintype "passive"))
      (node (ref "TP616") (pin "1") (pinfunction "1_1") (pintype "passive"))
      (node (ref "TP617") (pin "1") (pinfunction "1_1") (pintype "passive"))
      (node (ref "TP625") (pin "1") (pinfunction "1_1") (pintype "passive"))
      (node (ref "U600") (pin "1") (pinfunction "GND_1") (pintype "power_in"))
      (node (ref "U600") (pin "5") (pinfunction "~{EN}_5") (pintype "input"))
      (node (ref "U600") (pin "7") (pinfunction "EP_7") (pintype "power_in"))
      (node (ref "U601") (pin "B2") (pinfunction "V-_B2") (pintype "power_in"))
      (node (ref "U602") (pin "1") (pinfunction "GND_1") (pintype "power_in"))
      (node (ref "U602") (pin "5") (pinfunction "~{EN}_5") (pintype "input"))
      (node (ref "U602") (pin "7") (pinfunction "EP_7") (pintype "power_in"))
      (node (ref "U603") (pin "B2") (pinfunction "V-_B2") (pintype "power_in"))
      (node (ref "U604") (pin "B1") (pinfunction "V-_B1") (pintype "power_in"))
      (node (ref "U605") (pin "B1") (pinfunction "V-_B1") (pintype "power_in"))
      (node (ref "U607") (pin "1") (pinfunction "1_1") (pintype "passive"))
      (node (ref "U608") (pin "1") (pinfunction "1_1") (pintype "passive"))
      (node (ref "U609") (pin "1") (pinfunction "1_1") (pintype "passive"))
      (node (ref "U610") (pin "1") (pinfunction "1_1") (pintype "passive"))
      (node (ref "U610") (pin "4") (pinfunction "4_4") (pintype "passive"))
      (node (ref "U611") (pin "1") (pinfunction "1_1") (pintype "passive"))
      (node (ref "U611") (pin "4") (pinfunction "4_4") (pintype "passive"))
      (node (ref "U613") (pin "1") (pinfunction "1_1") (pintype "passive"))
      (node (ref "U613") (pin "4") (pinfunction "4_4") (pintype "passive"))
      (node (ref "U615") (pin "1") (pinfunction "1_1") (pintype "passive"))
      (node (ref "U615") (pin "4") (pinfunction "4_4") (pintype "passive"))
    )
    (net (code "35") (name "Net-(D600-Pad2)") (class "Default")
      (node (ref "D600") (pin "2") (pinfunction "2_2") (pintype "passive"))
      (node (ref "U612") (pin "3") (pinfunction "3_3") (pintype "passive"))
      (node (ref "U612") (pin "6") (pinfunction "6_6") (pintype "passive"))
    )
    (net (code "36") (name "Net-(D601-A)") (class "Default")
      (node (ref "D601") (pin "2") (pinfunction "A_2") (pintype "passive"))
      (node (ref "R609") (pin "2") (pinfunction "2_2") (pintype "passive"))
      (node (ref "U606") (pin "5") (pinfunction "5_5") (pintype "passive"))
    )
    (net (code "37") (name "Net-(D602-Pad2)") (class "Default")
      (node (ref "D602") (pin "2") (pinfunction "2_2") (pintype "passive"))
      (node (ref "U614") (pin "3") (pinfunction "3_3") (pintype "passive"))
      (node (ref "U614") (pin "6") (pinfunction "6_6") (pintype "passive"))
    )
    (net (code "38") (name "Net-(D603-A)") (class "Default")
      (node (ref "D603") (pin "2") (pinfunction "A_2") (pintype "passive"))
      (node (ref "R615") (pin "2") (pinfunction "2_2") (pintype "passive"))
      (node (ref "U606") (pin "2") (pinfunction "2_2") (pintype "passive"))
    )
    (net (code "39") (name "Net-(D604-K)") (class "Default")
      (node (ref "D604") (pin "1") (pinfunction "K_1") (pintype "passive"))
      (node (ref "R623") (pin "1") (pinfunction "1_1") (pintype "passive"))
    )
    (net (code "40") (name "Net-(D605-A)") (class "Default")
      (node (ref "D605") (pin "2") (pinfunction "A_2") (pintype "passive"))
      (node (ref "R625") (pin "2") (pinfunction "2_2") (pintype "passive"))
      (node (ref "U616") (pin "5") (pinfunction "5_5") (pintype "passive"))
    )
    (net (code "41") (name "Net-(D605-K)") (class "Default")
      (node (ref "D605") (pin "1") (pinfunction "K_1") (pintype "passive"))
      (node (ref "D606") (pin "1") (pinfunction "K_1") (pintype "passive"))
      (node (ref "M622") (pin "3") (pinfunction "D_3") (pintype "passive"))
    )
    (net (code "42") (name "Net-(D606-A)") (class "Default")
      (node (ref "D606") (pin "2") (pinfunction "A_2") (pintype "passive"))
      (node (ref "R628") (pin "2") (pinfunction "2_2") (pintype "passive"))
      (node (ref "U616") (pin "2") (pinfunction "2_2") (pintype "passive"))
    )
    (net (code "43") (name "Net-(R600-Pad2)") (class "Default")
      (node (ref "R600") (pin "2") (pinfunction "2_2") (pintype "passive"))
      (node (ref "U608") (pin "5") (pinfunction "5_5") (pintype "passive"))
      (node (ref "U608") (pin "6") (pinfunction "6_6") (pintype "passive"))
    )
    (net (code "44") (name "Net-(R602-Pad2)") (class "Default")
      (node (ref "R602") (pin "2") (pinfunction "2_2") (pintype "passive"))
      (node (ref "U612") (pin "2") (pinfunction "2_2") (pintype "passive"))
      (node (ref "U613") (pin "3") (pinfunction "3_3") (pintype "passive"))
    )
    (net (code "45") (name "Net-(R605-Pad2)") (class "Default")
      (node (ref "R605") (pin "2") (pinfunction "2_2") (pintype "passive"))
      (node (ref "U611") (pin "3") (pinfunction "3_3") (pintype "passive"))
    )
    (net (code "46") (name "Net-(R606-Pad2)") (class "Default")
      (node (ref "R606") (pin "2") (pinfunction "2_2") (pintype "passive"))
      (node (ref "U611") (pin "6") (pinfunction "6_6") (pintype "passive"))
    )
    (net (code "47") (name "Net-(R611-Pad2)") (class "Default")
      (node (ref "R611") (pin "2") (pinfunction "2_2") (pintype "passive"))
      (node (ref "U609") (pin "5") (pinfunction "5_5") (pintype "passive"))
      (node (ref "U609") (pin "6") (pinfunction "6_6") (pintype "passive"))
    )
    (net (code "48") (name "Net-(R613-Pad2)") (class "Default")
      (node (ref "R613") (pin "2") (pinfunction "2_2") (pintype "passive"))
      (node (ref "U614") (pin "2") (pinfunction "2_2") (pintype "passive"))
      (node (ref "U615") (pin "3") (pinfunction "3_3") (pintype "passive"))
    )
    (net (code "49") (name "Net-(R618-Pad2)") (class "Default")
      (node (ref "R618") (pin "2") (pinfunction "2_2") (pintype "passive"))
      (node (ref "U610") (pin "3") (pinfunction "3_3") (pintype "passive"))
    )
    (net (code "50") (name "Net-(R619-Pad2)") (class "Default")
      (node (ref "R619") (pin "2") (pinfunction "2_2") (pintype "passive"))
      (node (ref "U610") (pin "6") (pinfunction "6_6") (pintype "passive"))
    )
    (net (code "51") (name "Net-(R620-Pad1)") (class "Default")
      (node (ref "R620") (pin "1") (pinfunction "1_1") (pintype "passive"))
      (node (ref "U607") (pin "6") (pinfunction "6_6") (pintype "passive"))
    )
    (net (code "52") (name "Net-(R626-Pad1)") (class "Default")
      (node (ref "R626") (pin "1") (pinfunction "1_1") (pintype "passive"))
      (node (ref "U616") (pin "3") (pinfunction "3_3") (pintype "passive"))
    )
    (net (code "53") (name "Net-(R629-Pad1)") (class "Default")
      (node (ref "R629") (pin "1") (pinfunction "1_1") (pintype "passive"))
      (node (ref "U616") (pin "6") (pinfunction "6_6") (pintype "passive"))
    )
    (net (code "54") (name "Net-(U600-PROG)") (class "Default")
      (node (ref "R604") (pin "1") (pinfunction "1_1") (pintype "passive"))
      (node (ref "R605") (pin "1") (pinfunction "1_1") (pintype "passive"))
      (node (ref "R606") (pin "1") (pinfunction "1_1") (pintype "passive"))
      (node (ref "U600") (pin "6") (pinfunction "PROG_6") (pintype "passive"))
    )
    (net (code "55") (name "Net-(U601-IN)") (class "Default")
      (node (ref "C602") (pin "2") (pinfunction "2_2") (pintype "passive"))
      (node (ref "R607") (pin "1") (pinfunction "1_1") (pintype "passive"))
      (node (ref "R610") (pin "2") (pinfunction "2_2") (pintype "passive"))
      (node (ref "U601") (pin "A2") (pinfunction "IN_A2") (pintype "passive"))
    )
    (net (code "56") (name "Net-(U602-PROG)") (class "Default")
      (node (ref "R617") (pin "1") (pinfunction "1_1") (pintype "passive"))
      (node (ref "R618") (pin "1") (pinfunction "1_1") (pintype "passive"))
      (node (ref "R619") (pin "1") (pinfunction "1_1") (pintype "passive"))
      (node (ref "U602") (pin "6") (pinfunction "PROG_6") (pintype "passive"))
    )
    (net (code "57") (name "Net-(U603-IN)") (class "Default")
      (node (ref "C605") (pin "2") (pinfunction "2_2") (pintype "passive"))
      (node (ref "R621") (pin "1") (pinfunction "1_1") (pintype "passive"))
      (node (ref "R622") (pin "2") (pinfunction "2_2") (pintype "passive"))
      (node (ref "U603") (pin "A2") (pinfunction "IN_A2") (pintype "passive"))
    )
    (net (code "58") (name "Net-(U604-IN+)") (class "Default")
      (node (ref "R626") (pin "2") (pinfunction "2_2") (pintype "passive"))
      (node (ref "R627") (pin "1") (pinfunction "1_1") (pintype "passive"))
      (node (ref "U604") (pin "C1") (pinfunction "IN+_C1") (pintype "passive"))
    )
    (net (code "59") (name "Net-(U605-IN+)") (class "Default")
      (node (ref "R629") (pin "2") (pinfunction "2_2") (pintype "passive"))
      (node (ref "R630") (pin "1") (pinfunction "1_1") (pintype "passive"))
      (node (ref "U605") (pin "C1") (pinfunction "IN+_C1") (pintype "passive"))
    )
    (net (code "60") (name "unconnected-(U604-NC-PadB2)") (class "Default")
      (node (ref "U604") (pin "B2") (pinfunction "NC_B2") (pintype "power_in+no_connect"))
    )
    (net (code "61") (name "unconnected-(U605-NC-PadB2)") (class "Default")
      (node (ref "U605") (pin "B2") (pinfunction "NC_B2") (pintype "power_in+no_connect"))
    )
    (net (code "62") (name "unconnected-(U607-Pad3)") (class "Default")
      (node (ref "U607") (pin "3") (pinfunction "3_3") (pintype "passive+no_connect"))
    )
    (net (code "63") (name "unconnected-(U607-Pad4)") (class "Default")
      (node (ref "U607") (pin "4") (pinfunction "4_4") (pintype "passive+no_connect"))
    )
    (net (code "64") (name "unconnected-(U607-Pad5)") (class "Default")
      (node (ref "U607") (pin "5") (pinfunction "5_5") (pintype "passive+no_connect"))
    )
  )
)
